# rev1_0_1.net
KiCad netlist of a schematic drawn in EAGLE
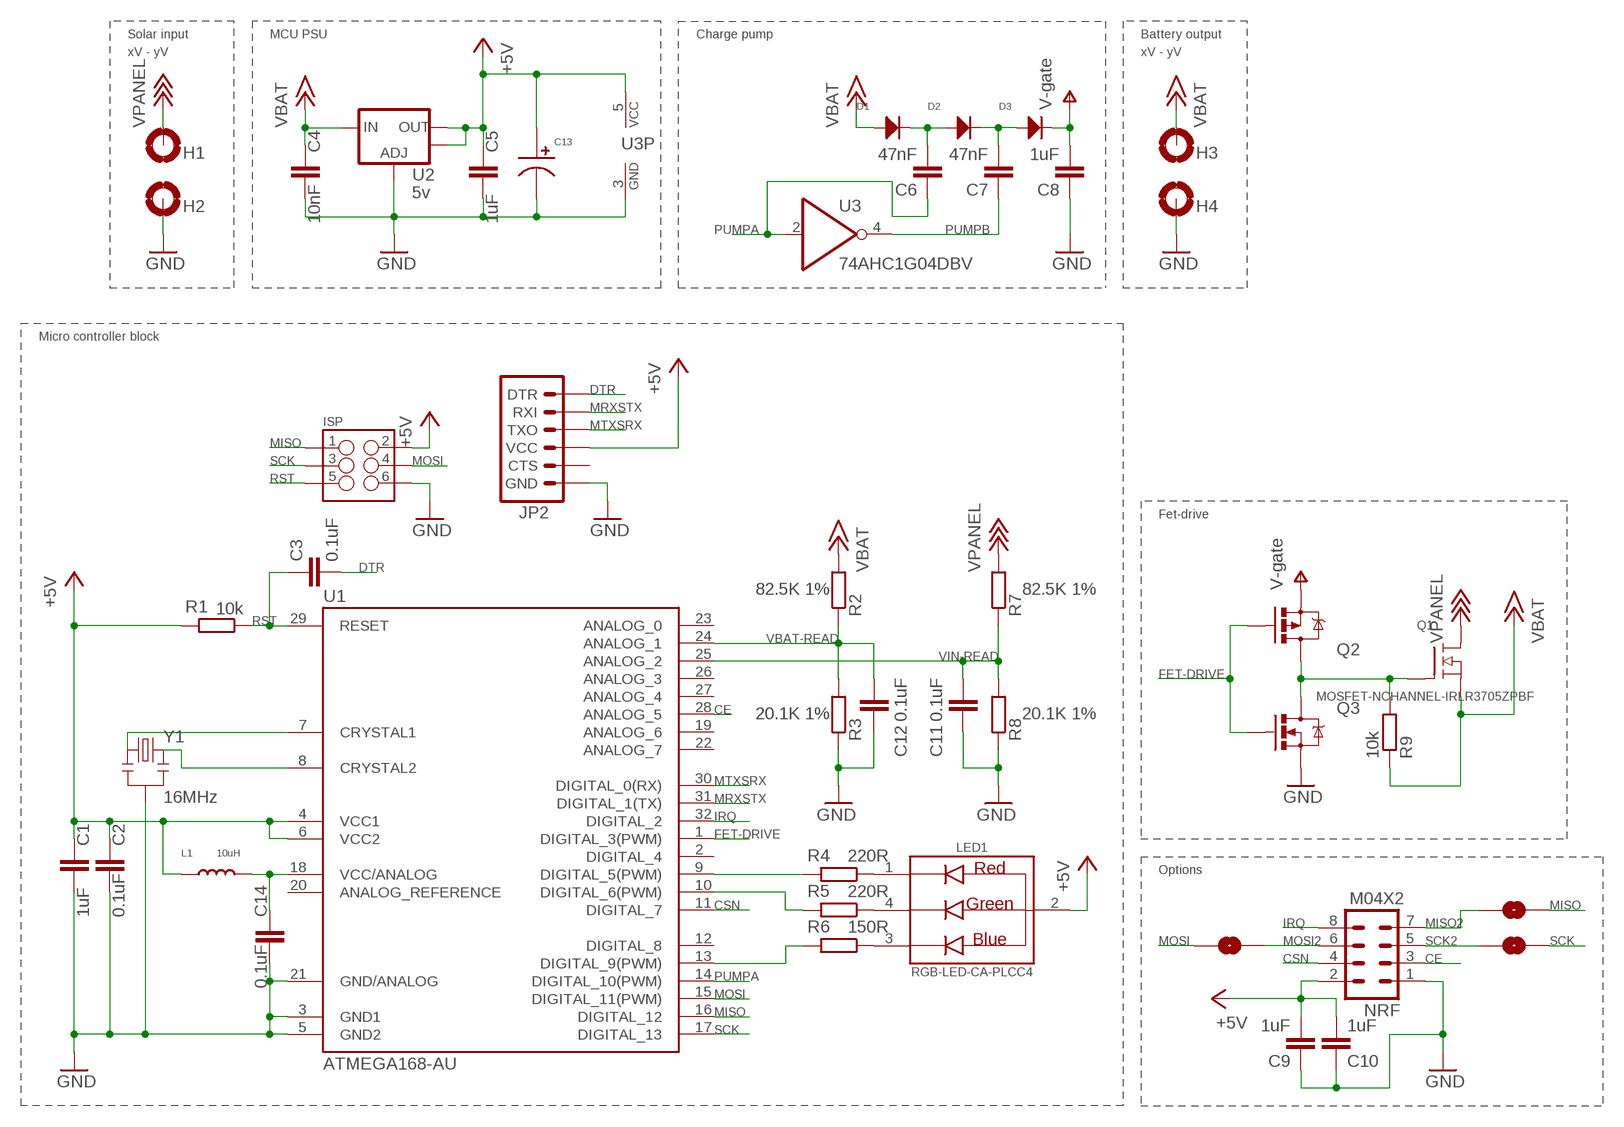
[diagram p0: schematic, sheet 1]

(export (version "E")
  (design (tool "Eeschema 10.0.6"))
  (components
    (comp (ref "C1")
      (value "1uF")
      (footprint "eagle-import:C0603K")
      (libsource (lib "eagle-import") (part "C-EUC0603K"))
    )
    (comp (ref "C2")
      (value "0.1uF")
      (footprint "eagle-import:C0603K")
      (libsource (lib "eagle-import") (part "C-EUC0603K"))
    )
    (comp (ref "C3")
      (value "0.1uF")
      (footprint "eagle-import:C0603K")
      (libsource (lib "eagle-import") (part "C-EUC0603K"))
    )
    (comp (ref "C4")
      (value "10nF")
      (footprint "eagle-import:C0603K")
      (libsource (lib "eagle-import") (part "C-EUC0603K"))
    )
    (comp (ref "C5")
      (value "1uF")
      (footprint "eagle-import:C0603K")
      (libsource (lib "eagle-import") (part "C-EUC0603K"))
    )
    (comp (ref "C6")
      (value "47nF")
      (footprint "eagle-import:C0603K")
      (libsource (lib "eagle-import") (part "C-EUC0603K"))
    )
    (comp (ref "C7")
      (value "47nF")
      (footprint "eagle-import:C0603K")
      (libsource (lib "eagle-import") (part "C-EUC0603K"))
    )
    (comp (ref "C8")
      (value "1uF")
      (footprint "eagle-import:C0603K")
      (libsource (lib "eagle-import") (part "C-EUC0603K"))
    )
    (comp (ref "C9")
      (value "1uF")
      (footprint "eagle-import:C0603K")
      (libsource (lib "eagle-import") (part "C-EUC0603K"))
    )
    (comp (ref "C10")
      (value "1uF")
      (footprint "eagle-import:C0603K")
      (libsource (lib "eagle-import") (part "C-EUC0603K"))
    )
    (comp (ref "C11")
      (value "0.1uF")
      (footprint "eagle-import:C0603K")
      (libsource (lib "eagle-import") (part "C-EUC0603K"))
    )
    (comp (ref "C12")
      (value "0.1uF")
      (footprint "eagle-import:C0603K")
      (libsource (lib "eagle-import") (part "C-EUC0603K"))
    )
    (comp (ref "C13")
      (value "CAPACITOR_P_4MM")
      (footprint "eagle-import:CP4MM")
      (libsource (lib "eagle-import") (part "CAPACITOR_P_4MM"))
    )
    (comp (ref "C14")
      (value "0.1uF")
      (footprint "eagle-import:C0603K")
      (libsource (lib "eagle-import") (part "C-EUC0603K"))
    )
    (comp (ref "D1")
      (value "DIODE_SOD-123")
      (footprint "eagle-import:SOD-123")
      (libsource (lib "eagle-import") (part "DIODE_SOD-123"))
    )
    (comp (ref "D2")
      (value "DIODE_SOD-123")
      (footprint "eagle-import:SOD-123")
      (libsource (lib "eagle-import") (part "DIODE_SOD-123"))
    )
    (comp (ref "D3")
      (value "DIODE_SOD-123")
      (footprint "eagle-import:SOD-123")
      (libsource (lib "eagle-import") (part "DIODE_SOD-123"))
    )
    (comp (ref "H1")
      (value "MOUNT-PAD-ROUND3.0")
      (footprint "eagle-import:3,0-PAD")
      (libsource (lib "eagle-import") (part "MOUNT-PAD-ROUND3.0"))
    )
    (comp (ref "H2")
      (value "MOUNT-PAD-ROUND3.0")
      (footprint "eagle-import:3,0-PAD")
      (libsource (lib "eagle-import") (part "MOUNT-PAD-ROUND3.0"))
    )
    (comp (ref "H3")
      (value "MOUNT-PAD-ROUND3.0")
      (footprint "eagle-import:3,0-PAD")
      (libsource (lib "eagle-import") (part "MOUNT-PAD-ROUND3.0"))
    )
    (comp (ref "H4")
      (value "MOUNT-PAD-ROUND3.0")
      (footprint "eagle-import:3,0-PAD")
      (libsource (lib "eagle-import") (part "MOUNT-PAD-ROUND3.0"))
    )
    (comp (ref "ISP")
      (value "M03X22X3_SILK_SM")
      (footprint "eagle-import:2X3")
      (libsource (lib "eagle-import") (part "M03X22X3_SILK_SM"))
    )
    (comp (ref "JP2")
      (value "ARDUINO_SERIAL_PROGRAMLOCK")
      (footprint "eagle-import:1X06_LOCK")
      (libsource (lib "eagle-import") (part "ARDUINO_SERIAL_PROGRAMLOCK"))
    )
    (comp (ref "L1")
      (value "10uH")
      (footprint "eagle-import:L1210")
      (libsource (lib "eagle-import") (part "INDUCTOR_1210"))
    )
    (comp (ref "LED1")
      (value "RGB-LED-CA-PLCC4")
      (footprint "eagle-import:PLCC4")
      (libsource (lib "eagle-import") (part "RGB-LED-CA-PLCC4"))
    )
    (comp (ref "NRF")
      (value "M04X2")
      (footprint "eagle-import:2X4")
      (libsource (lib "eagle-import") (part "M04X2"))
    )
    (comp (ref "Q1")
      (value "MOSFET-NCHANNEL-IRLR3705ZPBF")
      (footprint "eagle-import:DPAK")
      (libsource (lib "eagle-import") (part "MOSFET-NCHANNEL-IRLR3705ZPBF"))
    )
    (comp (ref "Q2")
      (value "MOSFET-PCHANNEL")
      (footprint "eagle-import:SOT23")
      (libsource (lib "eagle-import") (part "MOSFET-PCHANNEL"))
    )
    (comp (ref "Q3")
      (value "MOSFET-NCHANNELBSS138")
      (footprint "eagle-import:SOT23")
      (libsource (lib "eagle-import") (part "MOSFET-NCHANNELBSS138"))
    )
    (comp (ref "R1")
      (value "10k")
      (footprint "eagle-import:R0603")
      (libsource (lib "eagle-import") (part "R-EU_R0603"))
    )
    (comp (ref "R2")
      (value "82.5K 1%")
      (footprint "eagle-import:R0603")
      (libsource (lib "eagle-import") (part "R-EU_R0603"))
    )
    (comp (ref "R3")
      (value "20.1K 1%")
      (footprint "eagle-import:R0603")
      (libsource (lib "eagle-import") (part "R-EU_R0603"))
    )
    (comp (ref "R4")
      (value "220R")
      (footprint "eagle-import:R0603")
      (libsource (lib "eagle-import") (part "R-EU_R0603"))
    )
    (comp (ref "R5")
      (value "220R")
      (footprint "eagle-import:R0603")
      (libsource (lib "eagle-import") (part "R-EU_R0603"))
    )
    (comp (ref "R6")
      (value "150R")
      (footprint "eagle-import:R0603")
      (libsource (lib "eagle-import") (part "R-EU_R0603"))
    )
    (comp (ref "R7")
      (value "82.5K 1%")
      (footprint "eagle-import:R0603")
      (libsource (lib "eagle-import") (part "R-EU_R0603"))
    )
    (comp (ref "R8")
      (value "20.1K 1%")
      (footprint "eagle-import:R0603")
      (libsource (lib "eagle-import") (part "R-EU_R0603"))
    )
    (comp (ref "R9")
      (value "10k")
      (footprint "eagle-import:R0603")
      (libsource (lib "eagle-import") (part "R-EU_R0603"))
    )
    (comp (ref "SJ2")
      (value "SOLDERJUMPERNO")
      (footprint "eagle-import:SJ_2S-NO")
      (libsource (lib "eagle-import") (part "SOLDERJUMPERNO"))
    )
    (comp (ref "SJ5")
      (value "SOLDERJUMPERNO")
      (footprint "eagle-import:SJ_2S-NO")
      (libsource (lib "eagle-import") (part "SOLDERJUMPERNO"))
    )
    (comp (ref "SJ6")
      (value "SOLDERJUMPERNO")
      (footprint "eagle-import:SJ_2S-NO")
      (libsource (lib "eagle-import") (part "SOLDERJUMPERNO"))
    )
    (comp (ref "U1")
      (value "ATMEGA168-AU")
      (footprint "eagle-import:TQFP32-08")
      (libsource (lib "eagle-import") (part "ATMEGA168-AU"))
    )
    (comp (ref "U2")
      (value "5v")
      (footprint "eagle-import:SOT223")
      (libsource (lib "eagle-import") (part "V_REG_LM1117SOT223"))
    )
    (comp (ref "U3")
      (value "74AHC1G04DBV")
      (footprint "eagle-import:SOT23-5")
      (libsource (lib "eagle-import") (part "741G04DBVAHC"))
    )
    (comp (ref "Y1")
      (value "16MHz")
      (footprint "eagle-import:RESONATOR-SMD")
      (libsource (lib "eagle-import") (part "RESONATOR16MHZ"))
    )
  )
  (nets
    (net (code "1") (name "+5V") (class "Default")
      (node (ref "C1") (pin "1") (pinfunction "1_1") (pintype "passive"))
      (node (ref "C10") (pin "2") (pinfunction "2_2") (pintype "passive"))
      (node (ref "C13") (pin "P$1") (pinfunction "P$1_P$1") (pintype "passive"))
      (node (ref "C2") (pin "1") (pinfunction "1_1") (pintype "passive"))
      (node (ref "C5") (pin "1") (pinfunction "1_1") (pintype "passive"))
      (node (ref "C9") (pin "2") (pinfunction "2_2") (pintype "passive"))
      (node (ref "ISP") (pin "2") (pinfunction "2_2") (pintype "bidirectional"))
      (node (ref "JP2") (pin "4") (pinfunction "VCC_4") (pintype "passive"))
      (node (ref "L1") (pin "P$1") (pinfunction "P$1_P$1") (pintype "passive"))
      (node (ref "LED1") (pin "2") (pinfunction "CA_2") (pintype "bidirectional"))
      (node (ref "NRF") (pin "2") (pinfunction "2_2") (pintype "passive"))
      (node (ref "R1") (pin "2") (pinfunction "2_2") (pintype "passive"))
      (node (ref "U1") (pin "4") (pinfunction "VCC1_4") (pintype "power_in"))
      (node (ref "U1") (pin "6") (pinfunction "VCC2_6") (pintype "power_in"))
      (node (ref "U2") (pin "2") (pinfunction "OUT_2") (pintype "output"))
      (node (ref "U2") (pin "4") (pinfunction "OUT_4") (pintype "output"))
      (node (ref "U3") (pin "5") (pinfunction "VCC_5") (pintype "power_in"))
    )
    (net (code "2") (name "/CE") (class "Default")
      (node (ref "NRF") (pin "3") (pinfunction "3_3") (pintype "passive"))
      (node (ref "U1") (pin "28") (pinfunction "ANALOG_5_28") (pintype "bidirectional"))
    )
    (net (code "3") (name "/CSN") (class "Default")
      (node (ref "NRF") (pin "4") (pinfunction "4_4") (pintype "passive"))
      (node (ref "U1") (pin "11") (pinfunction "DIGITAL_7_11") (pintype "bidirectional"))
    )
    (net (code "4") (name "/DTR") (class "Default")
      (node (ref "C3") (pin "2") (pinfunction "2_2") (pintype "passive"))
      (node (ref "JP2") (pin "1") (pinfunction "DTR_1") (pintype "passive"))
    )
    (net (code "5") (name "/FET-DRIVE") (class "Default")
      (node (ref "Q2") (pin "1") (pinfunction "G_1") (pintype "passive"))
      (node (ref "Q3") (pin "1") (pinfunction "G_1") (pintype "passive"))
      (node (ref "U1") (pin "1") (pinfunction "DIGITAL_3(PWM)_1") (pintype "bidirectional"))
    )
    (net (code "6") (name "/IRQ") (class "Default")
      (node (ref "NRF") (pin "8") (pinfunction "8_8") (pintype "passive"))
      (node (ref "U1") (pin "32") (pinfunction "DIGITAL_2_32") (pintype "bidirectional"))
    )
    (net (code "7") (name "/MISO") (class "Default")
      (node (ref "ISP") (pin "1") (pinfunction "1_1") (pintype "bidirectional"))
      (node (ref "SJ6") (pin "2") (pinfunction "2_2") (pintype "passive"))
      (node (ref "U1") (pin "16") (pinfunction "DIGITAL_12_16") (pintype "bidirectional"))
    )
    (net (code "8") (name "/MISO2") (class "Default")
      (node (ref "NRF") (pin "7") (pinfunction "7_7") (pintype "passive"))
      (node (ref "SJ6") (pin "1") (pinfunction "1_1") (pintype "passive"))
    )
    (net (code "9") (name "/MOSI") (class "Default")
      (node (ref "ISP") (pin "4") (pinfunction "4_4") (pintype "bidirectional"))
      (node (ref "SJ2") (pin "1") (pinfunction "1_1") (pintype "passive"))
      (node (ref "U1") (pin "15") (pinfunction "DIGITAL_11(PWM)_15") (pintype "bidirectional"))
    )
    (net (code "10") (name "/MOSI2") (class "Default")
      (node (ref "NRF") (pin "6") (pinfunction "6_6") (pintype "passive"))
      (node (ref "SJ2") (pin "2") (pinfunction "2_2") (pintype "passive"))
    )
    (net (code "11") (name "/MRXSTX") (class "Default")
      (node (ref "JP2") (pin "2") (pinfunction "RXI_2") (pintype "passive"))
      (node (ref "U1") (pin "31") (pinfunction "DIGITAL_1(TX)_31") (pintype "bidirectional"))
    )
    (net (code "12") (name "/MTXSRX") (class "Default")
      (node (ref "JP2") (pin "3") (pinfunction "TXO_3") (pintype "passive"))
      (node (ref "U1") (pin "30") (pinfunction "DIGITAL_0(RX)_30") (pintype "bidirectional"))
    )
    (net (code "13") (name "/PUMPA") (class "Default")
      (node (ref "C6") (pin "1") (pinfunction "1_1") (pintype "passive"))
      (node (ref "U1") (pin "14") (pinfunction "DIGITAL_10(PWM)_14") (pintype "bidirectional"))
      (node (ref "U3") (pin "2") (pinfunction "I_2") (pintype "input"))
    )
    (net (code "14") (name "/PUMPB") (class "Default")
      (node (ref "C7") (pin "1") (pinfunction "1_1") (pintype "passive"))
      (node (ref "U3") (pin "4") (pinfunction "O_4") (pintype "output"))
    )
    (net (code "15") (name "/RST") (class "Default")
      (node (ref "C3") (pin "1") (pinfunction "1_1") (pintype "passive"))
      (node (ref "ISP") (pin "5") (pinfunction "5_5") (pintype "bidirectional"))
      (node (ref "R1") (pin "1") (pinfunction "1_1") (pintype "passive"))
      (node (ref "U1") (pin "29") (pinfunction "RESET_29") (pintype "bidirectional"))
    )
    (net (code "16") (name "/SCK") (class "Default")
      (node (ref "ISP") (pin "3") (pinfunction "3_3") (pintype "bidirectional"))
      (node (ref "SJ5") (pin "2") (pinfunction "2_2") (pintype "passive"))
      (node (ref "U1") (pin "17") (pinfunction "DIGITAL_13_17") (pintype "bidirectional"))
    )
    (net (code "17") (name "/SCK2") (class "Default")
      (node (ref "NRF") (pin "5") (pinfunction "5_5") (pintype "passive"))
      (node (ref "SJ5") (pin "1") (pinfunction "1_1") (pintype "passive"))
    )
    (net (code "18") (name "/VBAT-READ") (class "Default")
      (node (ref "C12") (pin "2") (pinfunction "2_2") (pintype "passive"))
      (node (ref "R2") (pin "1") (pinfunction "1_1") (pintype "passive"))
      (node (ref "R3") (pin "2") (pinfunction "2_2") (pintype "passive"))
      (node (ref "U1") (pin "24") (pinfunction "ANALOG_1_24") (pintype "bidirectional"))
    )
    (net (code "19") (name "/VIN-READ") (class "Default")
      (node (ref "C11") (pin "2") (pinfunction "2_2") (pintype "passive"))
      (node (ref "R7") (pin "1") (pinfunction "1_1") (pintype "passive"))
      (node (ref "R8") (pin "2") (pinfunction "2_2") (pintype "passive"))
      (node (ref "U1") (pin "25") (pinfunction "ANALOG_2_25") (pintype "bidirectional"))
    )
    (net (code "20") (name "GND") (class "Default")
      (node (ref "C1") (pin "2") (pinfunction "2_2") (pintype "passive"))
      (node (ref "C10") (pin "1") (pinfunction "1_1") (pintype "passive"))
      (node (ref "C11") (pin "1") (pinfunction "1_1") (pintype "passive"))
      (node (ref "C12") (pin "1") (pinfunction "1_1") (pintype "passive"))
      (node (ref "C13") (pin "P$2") (pinfunction "P$2_P$2") (pintype "passive"))
      (node (ref "C14") (pin "2") (pinfunction "2_2") (pintype "passive"))
      (node (ref "C2") (pin "2") (pinfunction "2_2") (pintype "passive"))
      (node (ref "C4") (pin "2") (pinfunction "2_2") (pintype "passive"))
      (node (ref "C5") (pin "2") (pinfunction "2_2") (pintype "passive"))
      (node (ref "C8") (pin "1") (pinfunction "1_1") (pintype "passive"))
      (node (ref "C9") (pin "1") (pinfunction "1_1") (pintype "passive"))
      (node (ref "H2") (pin "B3,0") (pinfunction "MOUNT_B3,0") (pintype "passive"))
      (node (ref "H4") (pin "B3,0") (pinfunction "MOUNT_B3,0") (pintype "passive"))
      (node (ref "ISP") (pin "6") (pinfunction "6_6") (pintype "bidirectional"))
      (node (ref "JP2") (pin "6") (pinfunction "GND_6") (pintype "passive"))
      (node (ref "NRF") (pin "1") (pinfunction "1_1") (pintype "passive"))
      (node (ref "Q3") (pin "2") (pinfunction "S_2") (pintype "passive"))
      (node (ref "R3") (pin "1") (pinfunction "1_1") (pintype "passive"))
      (node (ref "R8") (pin "1") (pinfunction "1_1") (pintype "passive"))
      (node (ref "U1") (pin "21") (pinfunction "GND/ANALOG_21") (pintype "power_in"))
      (node (ref "U1") (pin "3") (pinfunction "GND1_3") (pintype "power_in"))
      (node (ref "U1") (pin "5") (pinfunction "GND2_5") (pintype "power_in"))
      (node (ref "U2") (pin "1") (pinfunction "ADJ_1") (pintype "input"))
      (node (ref "U3") (pin "3") (pinfunction "GND_3") (pintype "power_in"))
      (node (ref "Y1") (pin "2") (pinfunction "2_2") (pintype "passive"))
    )
    (net (code "21") (name "Net-(C6-Pad2)") (class "Default")
      (node (ref "C6") (pin "2") (pinfunction "2_2") (pintype "passive"))
      (node (ref "D1") (pin "CATHODE") (pinfunction "CATHODE_CATHODE") (pintype "bidirectional"))
      (node (ref "D2") (pin "ANODE") (pinfunction "ANODE_ANODE") (pintype "bidirectional"))
    )
    (net (code "22") (name "Net-(C7-Pad2)") (class "Default")
      (node (ref "C7") (pin "2") (pinfunction "2_2") (pintype "passive"))
      (node (ref "D2") (pin "CATHODE") (pinfunction "CATHODE_CATHODE") (pintype "bidirectional"))
      (node (ref "D3") (pin "ANODE") (pinfunction "ANODE_ANODE") (pintype "bidirectional"))
    )
    (net (code "23") (name "Net-(LED1-BC)") (class "Default")
      (node (ref "LED1") (pin "3") (pinfunction "BC_3") (pintype "bidirectional"))
      (node (ref "R6") (pin "1") (pinfunction "1_1") (pintype "passive"))
    )
    (net (code "24") (name "Net-(LED1-GC)") (class "Default")
      (node (ref "LED1") (pin "4") (pinfunction "GC_4") (pintype "bidirectional"))
      (node (ref "R5") (pin "1") (pinfunction "1_1") (pintype "passive"))
    )
    (net (code "25") (name "Net-(LED1-RC)") (class "Default")
      (node (ref "LED1") (pin "1") (pinfunction "RC_1") (pintype "bidirectional"))
      (node (ref "R4") (pin "1") (pinfunction "1_1") (pintype "passive"))
    )
    (net (code "26") (name "Net-(Q1-G)") (class "Default")
      (node (ref "Q1") (pin "1") (pinfunction "G_1") (pintype "bidirectional"))
      (node (ref "Q2") (pin "3") (pinfunction "D_3") (pintype "passive"))
      (node (ref "Q3") (pin "3") (pinfunction "D_3") (pintype "passive"))
      (node (ref "R9") (pin "2") (pinfunction "2_2") (pintype "passive"))
    )
    (net (code "27") (name "Net-(U1-CRYSTAL1)") (class "Default")
      (node (ref "U1") (pin "7") (pinfunction "CRYSTAL1_7") (pintype "bidirectional"))
      (node (ref "Y1") (pin "1") (pinfunction "1_1") (pintype "passive"))
    )
    (net (code "28") (name "Net-(U1-CRYSTAL2)") (class "Default")
      (node (ref "U1") (pin "8") (pinfunction "CRYSTAL2_8") (pintype "bidirectional"))
      (node (ref "Y1") (pin "3") (pinfunction "3_3") (pintype "passive"))
    )
    (net (code "29") (name "Net-(U1-DIGITAL_5(PWM))") (class "Default")
      (node (ref "R4") (pin "2") (pinfunction "2_2") (pintype "passive"))
      (node (ref "U1") (pin "9") (pinfunction "DIGITAL_5(PWM)_9") (pintype "bidirectional"))
    )
    (net (code "30") (name "Net-(U1-DIGITAL_6(PWM))") (class "Default")
      (node (ref "R5") (pin "2") (pinfunction "2_2") (pintype "passive"))
      (node (ref "U1") (pin "10") (pinfunction "DIGITAL_6(PWM)_10") (pintype "bidirectional"))
    )
    (net (code "31") (name "Net-(U1-DIGITAL_9(PWM))") (class "Default")
      (node (ref "R6") (pin "2") (pinfunction "2_2") (pintype "passive"))
      (node (ref "U1") (pin "13") (pinfunction "DIGITAL_9(PWM)_13") (pintype "bidirectional"))
    )
    (net (code "32") (name "Net-(U1-VCC{slash}ANALOG)") (class "Default")
      (node (ref "C14") (pin "1") (pinfunction "1_1") (pintype "passive"))
      (node (ref "L1") (pin "P$2") (pinfunction "P$2_P$2") (pintype "passive"))
      (node (ref "U1") (pin "18") (pinfunction "VCC/ANALOG_18") (pintype "passive"))
    )
    (net (code "33") (name "V-gate") (class "Default")
      (node (ref "C8") (pin "2") (pinfunction "2_2") (pintype "passive"))
      (node (ref "D3") (pin "CATHODE") (pinfunction "CATHODE_CATHODE") (pintype "bidirectional"))
      (node (ref "Q2") (pin "2") (pinfunction "S_2") (pintype "passive"))
    )
    (net (code "34") (name "VBAT") (class "Default")
      (node (ref "C4") (pin "1") (pinfunction "1_1") (pintype "passive"))
      (node (ref "D1") (pin "ANODE") (pinfunction "ANODE_ANODE") (pintype "bidirectional"))
      (node (ref "H3") (pin "B3,0") (pinfunction "MOUNT_B3,0") (pintype "passive"))
      (node (ref "Q1") (pin "2") (pinfunction "S_2") (pintype "bidirectional"))
      (node (ref "R2") (pin "2") (pinfunction "2_2") (pintype "passive"))
      (node (ref "R9") (pin "1") (pinfunction "1_1") (pintype "passive"))
      (node (ref "U2") (pin "3") (pinfunction "IN_3") (pintype "input"))
    )
    (net (code "35") (name "VPANEL") (class "Default")
      (node (ref "H1") (pin "B3,0") (pinfunction "MOUNT_B3,0") (pintype "passive"))
      (node (ref "Q1") (pin "TAB") (pinfunction "D_TAB") (pintype "bidirectional"))
      (node (ref "R7") (pin "2") (pinfunction "2_2") (pintype "passive"))
    )
    (net (code "36") (name "unconnected-(JP2-CTS-Pad5)") (class "Default")
      (node (ref "JP2") (pin "5") (pinfunction "CTS_5") (pintype "passive"))
    )
    (net (code "37") (name "unconnected-(U1-ANALOG_0-Pad23)") (class "Default")
      (node (ref "U1") (pin "23") (pinfunction "ANALOG_0_23") (pintype "bidirectional"))
    )
    (net (code "38") (name "unconnected-(U1-ANALOG_3-Pad26)") (class "Default")
      (node (ref "U1") (pin "26") (pinfunction "ANALOG_3_26") (pintype "bidirectional"))
    )
    (net (code "39") (name "unconnected-(U1-ANALOG_4-Pad27)") (class "Default")
      (node (ref "U1") (pin "27") (pinfunction "ANALOG_4_27") (pintype "bidirectional"))
    )
    (net (code "40") (name "unconnected-(U1-ANALOG_6-Pad19)") (class "Default")
      (node (ref "U1") (pin "19") (pinfunction "ANALOG_6_19") (pintype "passive"))
    )
    (net (code "41") (name "unconnected-(U1-ANALOG_7-Pad22)") (class "Default")
      (node (ref "U1") (pin "22") (pinfunction "ANALOG_7_22") (pintype "passive"))
    )
    (net (code "42") (name "unconnected-(U1-ANALOG_REFERENCE-Pad20)") (class "Default")
      (node (ref "U1") (pin "20") (pinfunction "ANALOG_REFERENCE_20") (pintype "passive"))
    )
    (net (code "43") (name "unconnected-(U1-DIGITAL_4-Pad2)") (class "Default")
      (node (ref "U1") (pin "2") (pinfunction "DIGITAL_4_2") (pintype "bidirectional"))
    )
    (net (code "44") (name "unconnected-(U1-DIGITAL_8-Pad12)") (class "Default")
      (node (ref "U1") (pin "12") (pinfunction "DIGITAL_8_12") (pintype "bidirectional"))
    )
  )
)
